# CLK_1_1.net
KiCad netlist of a schematic drawn in EAGLE
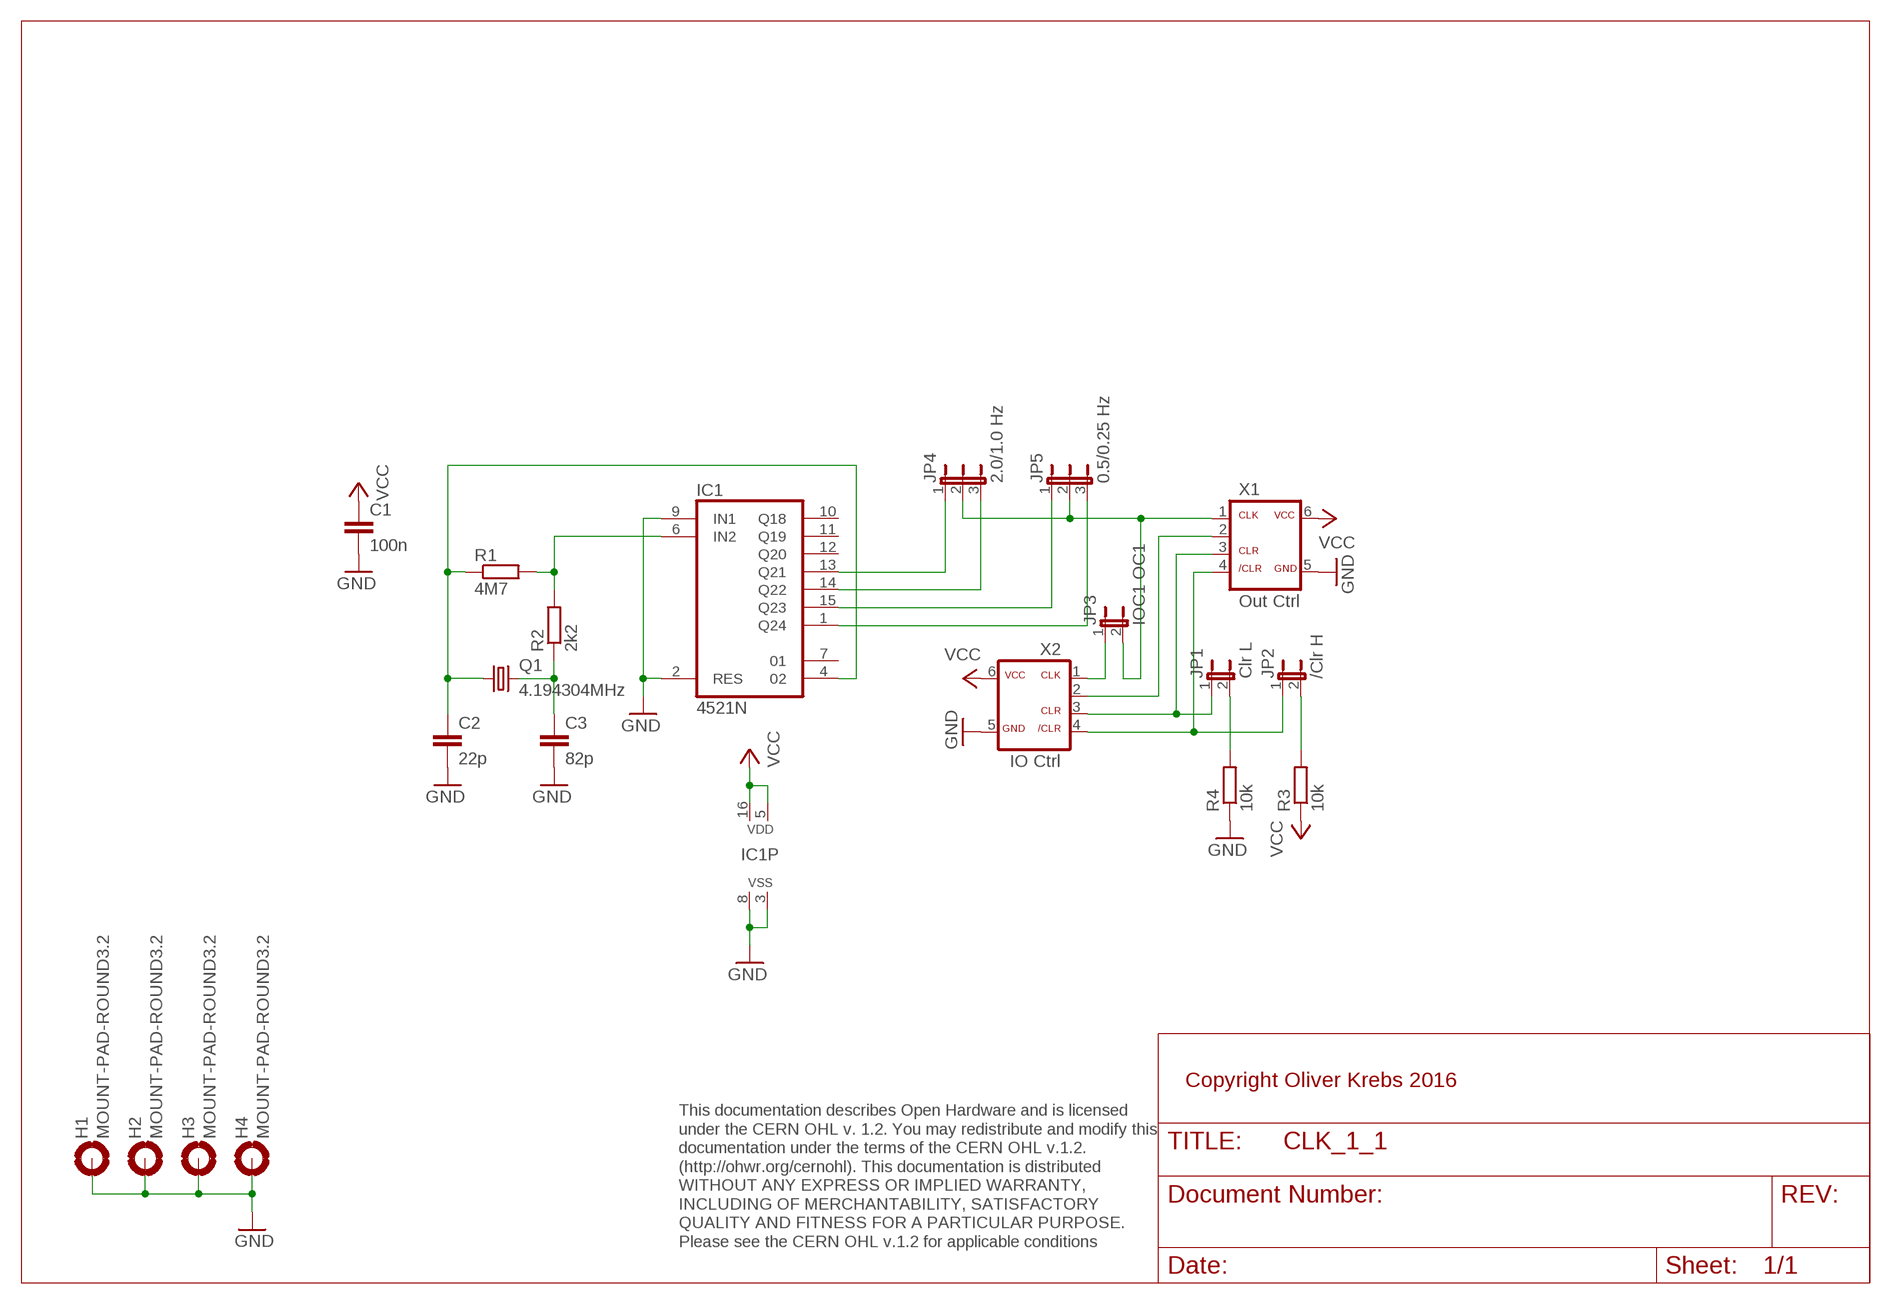
[diagram p0: schematic, sheet 1]

(export (version "E")
  (design (tool "Eeschema 10.0.6"))
  (components
    (comp (ref "C1")
      (value "100n")
      (footprint "eagle-import:C050-025X075")
      (libsource (lib "eagle-import") (part "C-EU050-025X075"))
    )
    (comp (ref "C2")
      (value "22p")
      (footprint "eagle-import:C050-025X075")
      (libsource (lib "eagle-import") (part "C-EU050-025X075"))
    )
    (comp (ref "C3")
      (value "82p")
      (footprint "eagle-import:C050-025X075")
      (libsource (lib "eagle-import") (part "C-EU050-025X075"))
    )
    (comp (ref "H1")
      (value "MOUNT-PAD-ROUND3.2")
      (footprint "eagle-import:3,2-PAD")
      (libsource (lib "eagle-import") (part "MOUNT-PAD-ROUND3.2"))
    )
    (comp (ref "H2")
      (value "MOUNT-PAD-ROUND3.2")
      (footprint "eagle-import:3,2-PAD")
      (libsource (lib "eagle-import") (part "MOUNT-PAD-ROUND3.2"))
    )
    (comp (ref "H3")
      (value "MOUNT-PAD-ROUND3.2")
      (footprint "eagle-import:3,2-PAD")
      (libsource (lib "eagle-import") (part "MOUNT-PAD-ROUND3.2"))
    )
    (comp (ref "H4")
      (value "MOUNT-PAD-ROUND3.2")
      (footprint "eagle-import:3,2-PAD")
      (libsource (lib "eagle-import") (part "MOUNT-PAD-ROUND3.2"))
    )
    (comp (ref "IC1")
      (value "4521N")
      (footprint "eagle-import:DIL16")
      (libsource (lib "eagle-import") (part "4521N"))
    )
    (comp (ref "JP1")
      (value "Clr L")
      (footprint "eagle-import:JP1")
      (libsource (lib "eagle-import") (part "JP1E"))
    )
    (comp (ref "JP2")
      (value "/Clr H")
      (footprint "eagle-import:JP1")
      (libsource (lib "eagle-import") (part "JP1E"))
    )
    (comp (ref "JP3")
      (value "IOC1 OC1")
      (footprint "eagle-import:JP1")
      (libsource (lib "eagle-import") (part "JP1E"))
    )
    (comp (ref "JP4")
      (value "2.0/1.0 Hz")
      (footprint "eagle-import:JP2-U")
      (libsource (lib "eagle-import") (part "JP2EJP2-U"))
    )
    (comp (ref "JP5")
      (value "0.5/0.25 Hz")
      (footprint "eagle-import:JP2-U")
      (libsource (lib "eagle-import") (part "JP2EJP2-U"))
    )
    (comp (ref "Q1")
      (value "4.194304MHz")
      (footprint "eagle-import:HC49US")
      (libsource (lib "eagle-import") (part "CRYSTALHC49US"))
    )
    (comp (ref "R1")
      (value "4M7")
      (footprint "eagle-import:0207_10")
      (libsource (lib "eagle-import") (part "R-EU_0207/10"))
    )
    (comp (ref "R2")
      (value "2k2")
      (footprint "eagle-import:0207_10")
      (libsource (lib "eagle-import") (part "R-EU_0207/10"))
    )
    (comp (ref "R3")
      (value "10k")
      (footprint "eagle-import:0207_10")
      (libsource (lib "eagle-import") (part "R-EU_0207/10"))
    )
    (comp (ref "R4")
      (value "10k")
      (footprint "eagle-import:0207_10")
      (libsource (lib "eagle-import") (part "R-EU_0207/10"))
    )
    (comp (ref "X1")
      (value "Out Ctrl")
      (footprint "eagle-import:ML-6")
      (libsource (lib "eagle-import") (part "ML6C"))
    )
    (comp (ref "X2")
      (value "IO Ctrl")
      (footprint "eagle-import:ML-6")
      (libsource (lib "eagle-import") (part "ML6C"))
    )
  )
  (nets
    (net (code "1") (name "GND") (class "Default")
      (node (ref "C1") (pin "2") (pinfunction "2_2") (pintype "passive"))
      (node (ref "C2") (pin "2") (pinfunction "2_2") (pintype "passive"))
      (node (ref "C3") (pin "2") (pinfunction "2_2") (pintype "passive"))
      (node (ref "H1") (pin "B3,2") (pinfunction "MOUNT_B3,2") (pintype "passive"))
      (node (ref "H2") (pin "B3,2") (pinfunction "MOUNT_B3,2") (pintype "passive"))
      (node (ref "H3") (pin "B3,2") (pinfunction "MOUNT_B3,2") (pintype "passive"))
      (node (ref "H4") (pin "B3,2") (pinfunction "MOUNT_B3,2") (pintype "passive"))
      (node (ref "IC1") (pin "2") (pinfunction "RES_2") (pintype "input"))
      (node (ref "IC1") (pin "3") (pinfunction "VSS_3") (pintype "power_in"))
      (node (ref "IC1") (pin "8") (pinfunction "VSS_8") (pintype "power_in"))
      (node (ref "IC1") (pin "9") (pinfunction "IN1_9") (pintype "input"))
      (node (ref "R4") (pin "1") (pinfunction "1_1") (pintype "passive"))
      (node (ref "X1") (pin "5") (pinfunction "5_5") (pintype "passive"))
      (node (ref "X2") (pin "5") (pinfunction "5_5") (pintype "passive"))
    )
    (net (code "2") (name "Net-(C3-Pad1)") (class "Default")
      (node (ref "C3") (pin "1") (pinfunction "1_1") (pintype "passive"))
      (node (ref "Q1") (pin "2") (pinfunction "2_2") (pintype "passive"))
      (node (ref "R2") (pin "1") (pinfunction "1_1") (pintype "passive"))
    )
    (net (code "3") (name "Net-(IC1A-02)") (class "Default")
      (node (ref "C2") (pin "1") (pinfunction "1_1") (pintype "passive"))
      (node (ref "IC1") (pin "4") (pinfunction "02_4") (pintype "output"))
      (node (ref "Q1") (pin "1") (pinfunction "1_1") (pintype "passive"))
      (node (ref "R1") (pin "1") (pinfunction "1_1") (pintype "passive"))
    )
    (net (code "4") (name "Net-(IC1A-IN2)") (class "Default")
      (node (ref "IC1") (pin "6") (pinfunction "IN2_6") (pintype "input"))
      (node (ref "R1") (pin "2") (pinfunction "2_2") (pintype "passive"))
      (node (ref "R2") (pin "2") (pinfunction "2_2") (pintype "passive"))
    )
    (net (code "5") (name "Net-(IC1A-Q21)") (class "Default")
      (node (ref "IC1") (pin "13") (pinfunction "Q21_13") (pintype "output"))
      (node (ref "JP4") (pin "1") (pinfunction "1_1") (pintype "passive"))
    )
    (net (code "6") (name "Net-(IC1A-Q22)") (class "Default")
      (node (ref "IC1") (pin "14") (pinfunction "Q22_14") (pintype "output"))
      (node (ref "JP4") (pin "3") (pinfunction "3_3") (pintype "passive"))
    )
    (net (code "7") (name "Net-(IC1A-Q23)") (class "Default")
      (node (ref "IC1") (pin "15") (pinfunction "Q23_15") (pintype "output"))
      (node (ref "JP5") (pin "1") (pinfunction "1_1") (pintype "passive"))
    )
    (net (code "8") (name "Net-(IC1A-Q24)") (class "Default")
      (node (ref "IC1") (pin "1") (pinfunction "Q24_1") (pintype "output"))
      (node (ref "JP5") (pin "3") (pinfunction "3_3") (pintype "passive"))
    )
    (net (code "9") (name "Net-(JP1-Pad1)") (class "Default")
      (node (ref "JP1") (pin "1") (pinfunction "1_1") (pintype "passive"))
      (node (ref "X1") (pin "3") (pinfunction "3_3") (pintype "passive"))
      (node (ref "X2") (pin "3") (pinfunction "3_3") (pintype "passive"))
    )
    (net (code "10") (name "Net-(JP1-Pad2)") (class "Default")
      (node (ref "JP1") (pin "2") (pinfunction "2_2") (pintype "passive"))
      (node (ref "R4") (pin "2") (pinfunction "2_2") (pintype "passive"))
    )
    (net (code "11") (name "Net-(JP2-Pad1)") (class "Default")
      (node (ref "JP2") (pin "1") (pinfunction "1_1") (pintype "passive"))
      (node (ref "X1") (pin "4") (pinfunction "4_4") (pintype "passive"))
      (node (ref "X2") (pin "4") (pinfunction "4_4") (pintype "passive"))
    )
    (net (code "12") (name "Net-(JP2-Pad2)") (class "Default")
      (node (ref "JP2") (pin "2") (pinfunction "2_2") (pintype "passive"))
      (node (ref "R3") (pin "2") (pinfunction "2_2") (pintype "passive"))
    )
    (net (code "13") (name "Net-(JP3-Pad1)") (class "Default")
      (node (ref "JP3") (pin "1") (pinfunction "1_1") (pintype "passive"))
      (node (ref "X2") (pin "1") (pinfunction "1_1") (pintype "passive"))
    )
    (net (code "14") (name "Net-(JP3-Pad2)") (class "Default")
      (node (ref "JP3") (pin "2") (pinfunction "2_2") (pintype "passive"))
      (node (ref "JP4") (pin "2") (pinfunction "2_2") (pintype "passive"))
      (node (ref "JP5") (pin "2") (pinfunction "2_2") (pintype "passive"))
      (node (ref "X1") (pin "1") (pinfunction "1_1") (pintype "passive"))
    )
    (net (code "15") (name "Net-(X1-Pad2)") (class "Default")
      (node (ref "X1") (pin "2") (pinfunction "2_2") (pintype "passive"))
      (node (ref "X2") (pin "2") (pinfunction "2_2") (pintype "passive"))
    )
    (net (code "16") (name "VCC") (class "Default")
      (node (ref "C1") (pin "1") (pinfunction "1_1") (pintype "passive"))
      (node (ref "IC1") (pin "16") (pinfunction "VDD_16") (pintype "power_in"))
      (node (ref "IC1") (pin "5") (pinfunction "VDD_5") (pintype "power_in"))
      (node (ref "R3") (pin "1") (pinfunction "1_1") (pintype "passive"))
      (node (ref "X1") (pin "6") (pinfunction "6_6") (pintype "passive"))
      (node (ref "X2") (pin "6") (pinfunction "6_6") (pintype "passive"))
    )
    (net (code "17") (name "unconnected-(IC1A-01-Pad7)") (class "Default")
      (node (ref "IC1") (pin "7") (pinfunction "01_7") (pintype "output"))
    )
    (net (code "18") (name "unconnected-(IC1A-Q18-Pad10)") (class "Default")
      (node (ref "IC1") (pin "10") (pinfunction "Q18_10") (pintype "output"))
    )
    (net (code "19") (name "unconnected-(IC1A-Q19-Pad11)") (class "Default")
      (node (ref "IC1") (pin "11") (pinfunction "Q19_11") (pintype "output"))
    )
    (net (code "20") (name "unconnected-(IC1A-Q20-Pad12)") (class "Default")
      (node (ref "IC1") (pin "12") (pinfunction "Q20_12") (pintype "output"))
    )
  )
)
